# Cable_Tester.net
KiCad netlist of a schematic drawn in EAGLE
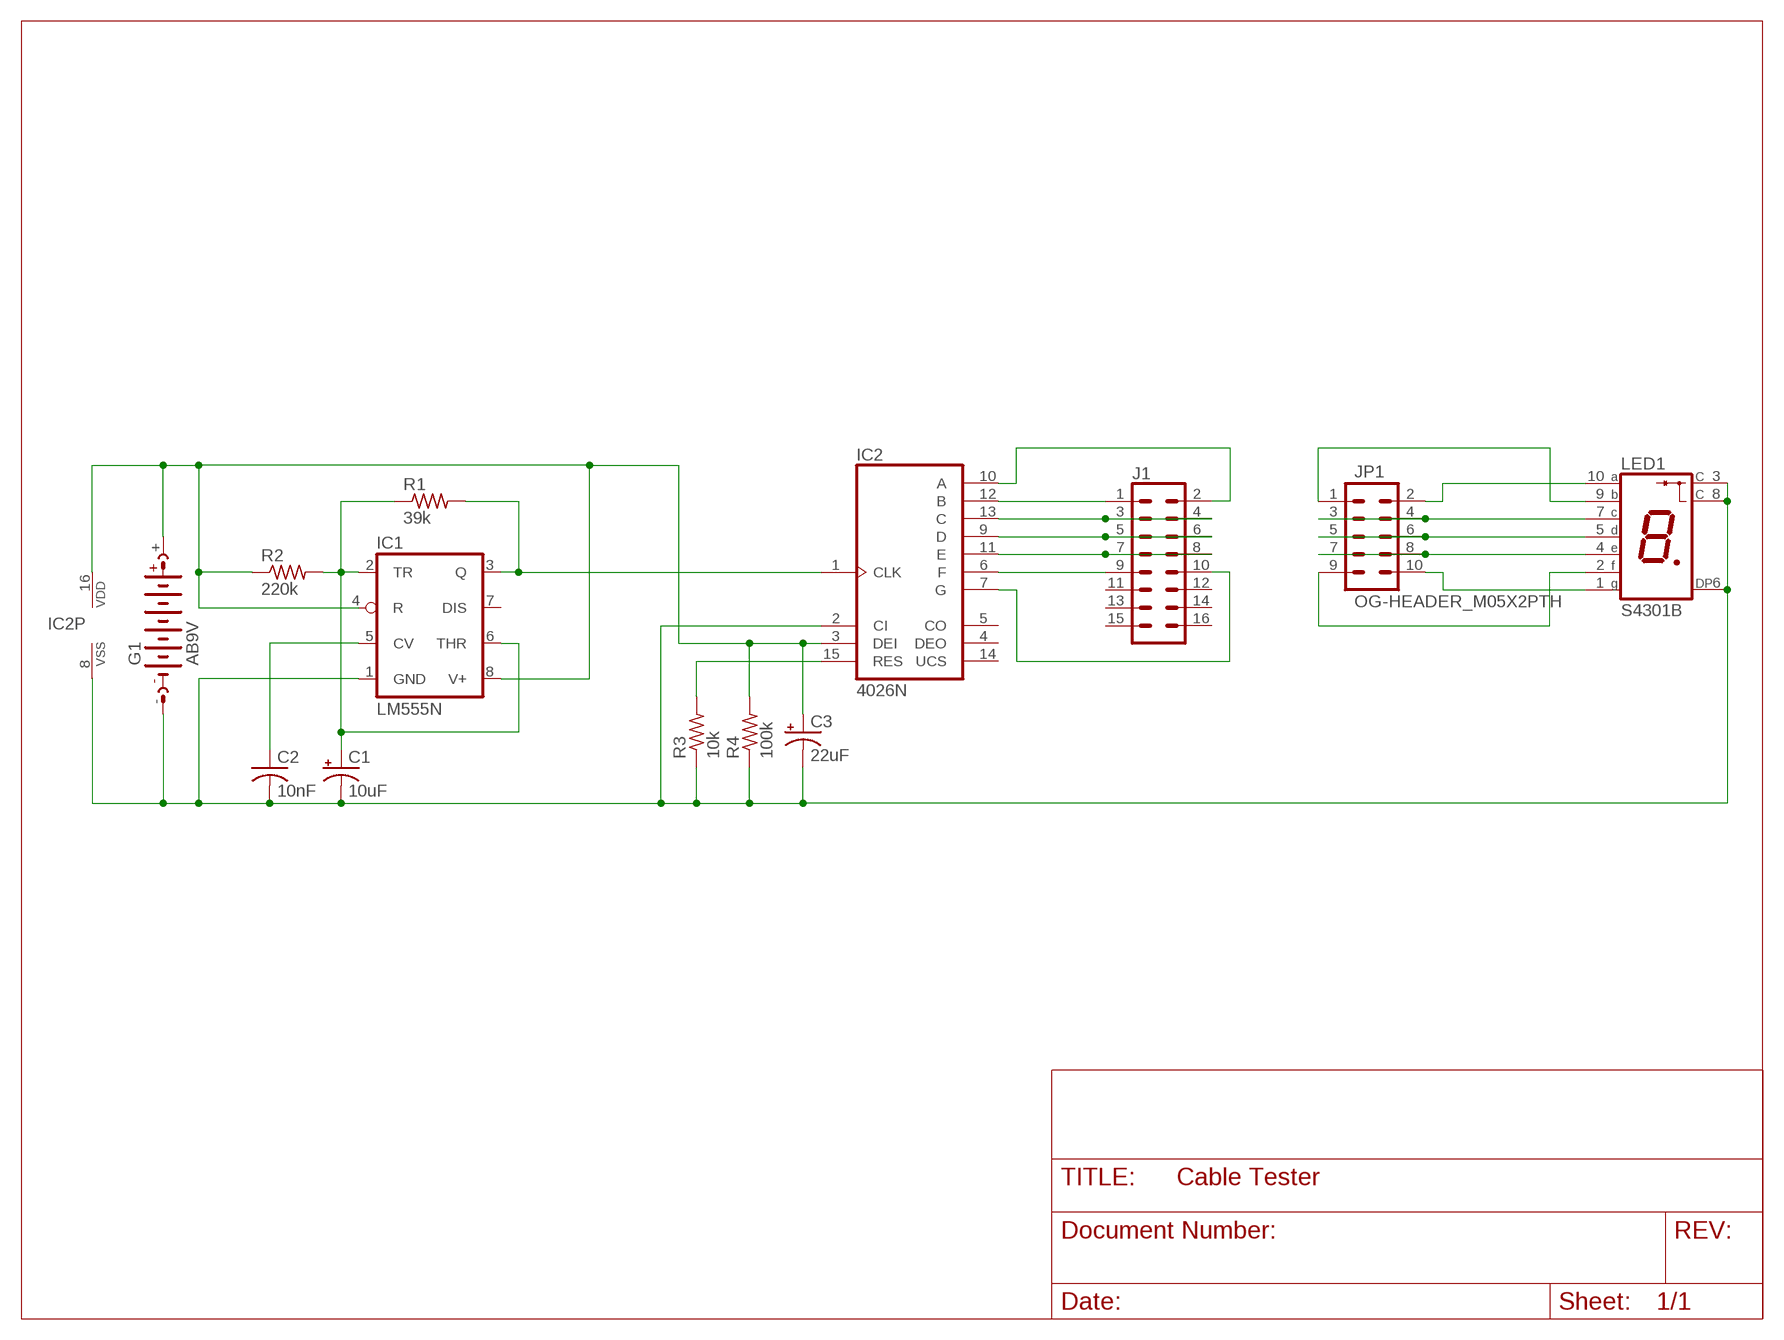
[diagram p0: schematic, sheet 1]

(export (version "E")
  (design (tool "Eeschema 10.0.6"))
  (components
    (comp (ref "C1")
      (value "10uF")
      (footprint "eagle-import:RCL_E5-5")
      (libsource (lib "eagle-import") (part "RCL_CPOL-USE5-5"))
    )
    (comp (ref "C2")
      (value "10nF")
      (footprint "eagle-import:RCL_C050-055X075")
      (libsource (lib "eagle-import") (part "RCL_C-US050-055X075"))
    )
    (comp (ref "C3")
      (value "22uF")
      (footprint "eagle-import:RCL_E5-5")
      (libsource (lib "eagle-import") (part "RCL_CPOL-USE5-5"))
    )
    (comp (ref "G1")
      (value "AB9V")
      (footprint "eagle-import:AB9V")
      (libsource (lib "eagle-import") (part "AB9V"))
    )
    (comp (ref "IC1")
      (value "LM555N")
      (footprint "eagle-import:DIL08")
      (libsource (lib "eagle-import") (part "555NLM"))
    )
    (comp (ref "IC2")
      (value "4026N")
      (footprint "eagle-import:DIL16")
      (libsource (lib "eagle-import") (part "4026N"))
    )
    (comp (ref "J1")
      (value "CONN_08X2_HEADER")
      (footprint "eagle-import:2X8")
      (libsource (lib "eagle-import") (part "CONN_08X2_HEADER"))
    )
    (comp (ref "JP1")
      (value "OG-HEADER_M05X2PTH")
      (footprint "eagle-import:OG-HEADER_AVR_ICSP")
      (libsource (lib "eagle-import") (part "OG-HEADER_M05X2PTH"))
    )
    (comp (ref "LED1")
      (value "S4301B")
      (footprint "eagle-import:S4301B")
      (libsource (lib "eagle-import") (part "S4301B"))
    )
    (comp (ref "R1")
      (value "39k")
      (footprint "eagle-import:RESISTOR_0309_10")
      (libsource (lib "eagle-import") (part "RESISTOR_R-US_0309/10"))
    )
    (comp (ref "R2")
      (value "220k")
      (footprint "eagle-import:RESISTOR_0309_10")
      (libsource (lib "eagle-import") (part "RESISTOR_R-US_0309/10"))
    )
    (comp (ref "R3")
      (value "10k")
      (footprint "eagle-import:RESISTOR_0309_10")
      (libsource (lib "eagle-import") (part "RESISTOR_R-US_0309/10"))
    )
    (comp (ref "R4")
      (value "100k")
      (footprint "eagle-import:RESISTOR_0309_10")
      (libsource (lib "eagle-import") (part "RESISTOR_R-US_0309/10"))
    )
  )
  (nets
    (net (code "1") (name "Net-(IC1-CV)") (class "Default")
      (node (ref "C2") (pin "1") (pinfunction "1_1") (pintype "passive"))
      (node (ref "IC1") (pin "5") (pinfunction "CV_5") (pintype "input"))
    )
    (net (code "2") (name "Net-(IC1-GND)") (class "Default")
      (node (ref "C1") (pin "-") (pinfunction "-_-") (pintype "passive"))
      (node (ref "C2") (pin "2") (pinfunction "2_2") (pintype "passive"))
      (node (ref "C3") (pin "-") (pinfunction "-_-") (pintype "passive"))
      (node (ref "G1") (pin "-") (pinfunction "-_-") (pintype "passive"))
      (node (ref "IC1") (pin "1") (pinfunction "GND_1") (pintype "power_in"))
      (node (ref "IC2") (pin "2") (pinfunction "CI_2") (pintype "input"))
      (node (ref "IC2") (pin "8") (pinfunction "VSS_8") (pintype "power_in"))
      (node (ref "LED1") (pin "3") (pinfunction "C_3") (pintype "passive"))
      (node (ref "LED1") (pin "6") (pinfunction "DP_6") (pintype "passive"))
      (node (ref "LED1") (pin "8") (pinfunction "C_8") (pintype "passive"))
      (node (ref "R3") (pin "1") (pinfunction "1_1") (pintype "passive"))
      (node (ref "R4") (pin "1") (pinfunction "1_1") (pintype "passive"))
    )
    (net (code "3") (name "Net-(IC1-Q)") (class "Default")
      (node (ref "IC1") (pin "3") (pinfunction "Q_3") (pintype "output"))
      (node (ref "IC2") (pin "1") (pinfunction "CLK_1") (pintype "input"))
      (node (ref "R1") (pin "2") (pinfunction "2_2") (pintype "passive"))
    )
    (net (code "4") (name "Net-(IC1-R)") (class "Default")
      (node (ref "C3") (pin "+") (pinfunction "+_+") (pintype "passive"))
      (node (ref "G1") (pin "+") (pinfunction "+_+") (pintype "passive"))
      (node (ref "IC1") (pin "4") (pinfunction "R_4") (pintype "input"))
      (node (ref "IC1") (pin "8") (pinfunction "V+_8") (pintype "power_in"))
      (node (ref "IC2") (pin "16") (pinfunction "VDD_16") (pintype "power_in"))
      (node (ref "IC2") (pin "3") (pinfunction "DEI_3") (pintype "input"))
      (node (ref "R2") (pin "1") (pinfunction "1_1") (pintype "passive"))
      (node (ref "R4") (pin "2") (pinfunction "2_2") (pintype "passive"))
    )
    (net (code "5") (name "Net-(IC1-THR)") (class "Default")
      (node (ref "C1") (pin "+") (pinfunction "+_+") (pintype "passive"))
      (node (ref "IC1") (pin "2") (pinfunction "TR_2") (pintype "input"))
      (node (ref "IC1") (pin "6") (pinfunction "THR_6") (pintype "input"))
      (node (ref "R1") (pin "1") (pinfunction "1_1") (pintype "passive"))
      (node (ref "R2") (pin "2") (pinfunction "2_2") (pintype "passive"))
    )
    (net (code "6") (name "Net-(IC2A-A)") (class "Default")
      (node (ref "IC2") (pin "10") (pinfunction "A_10") (pintype "output"))
      (node (ref "J1") (pin "2") (pinfunction "2_2") (pintype "passive"))
    )
    (net (code "7") (name "Net-(IC2A-B)") (class "Default")
      (node (ref "IC2") (pin "12") (pinfunction "B_12") (pintype "output"))
      (node (ref "J1") (pin "1") (pinfunction "1_1") (pintype "passive"))
    )
    (net (code "8") (name "Net-(IC2A-C)") (class "Default")
      (node (ref "IC2") (pin "13") (pinfunction "C_13") (pintype "output"))
      (node (ref "J1") (pin "3") (pinfunction "3_3") (pintype "passive"))
      (node (ref "J1") (pin "4") (pinfunction "4_4") (pintype "passive"))
    )
    (net (code "9") (name "Net-(IC2A-D)") (class "Default")
      (node (ref "IC2") (pin "9") (pinfunction "D_9") (pintype "output"))
      (node (ref "J1") (pin "5") (pinfunction "5_5") (pintype "passive"))
      (node (ref "J1") (pin "6") (pinfunction "6_6") (pintype "passive"))
    )
    (net (code "10") (name "Net-(IC2A-E)") (class "Default")
      (node (ref "IC2") (pin "11") (pinfunction "E_11") (pintype "output"))
      (node (ref "J1") (pin "7") (pinfunction "7_7") (pintype "passive"))
      (node (ref "J1") (pin "8") (pinfunction "8_8") (pintype "passive"))
    )
    (net (code "11") (name "Net-(IC2A-F)") (class "Default")
      (node (ref "IC2") (pin "6") (pinfunction "F_6") (pintype "output"))
      (node (ref "J1") (pin "9") (pinfunction "9_9") (pintype "passive"))
    )
    (net (code "12") (name "Net-(IC2A-G)") (class "Default")
      (node (ref "IC2") (pin "7") (pinfunction "G_7") (pintype "output"))
      (node (ref "J1") (pin "10") (pinfunction "10_10") (pintype "passive"))
    )
    (net (code "13") (name "Net-(IC2A-RES)") (class "Default")
      (node (ref "IC2") (pin "15") (pinfunction "RES_15") (pintype "input"))
      (node (ref "R3") (pin "2") (pinfunction "2_2") (pintype "passive"))
    )
    (net (code "14") (name "Net-(JP1-Pad3)") (class "Default")
      (node (ref "JP1") (pin "3") (pinfunction "3_3") (pintype "passive"))
      (node (ref "JP1") (pin "4") (pinfunction "4_4") (pintype "passive"))
      (node (ref "LED1") (pin "7") (pinfunction "C_7") (pintype "passive"))
    )
    (net (code "15") (name "Net-(LED1-A)") (class "Default")
      (node (ref "JP1") (pin "2") (pinfunction "2_2") (pintype "passive"))
      (node (ref "LED1") (pin "10") (pinfunction "A_10") (pintype "passive"))
    )
    (net (code "16") (name "Net-(LED1-B)") (class "Default")
      (node (ref "JP1") (pin "1") (pinfunction "1_1") (pintype "passive"))
      (node (ref "LED1") (pin "9") (pinfunction "B_9") (pintype "passive"))
    )
    (net (code "17") (name "Net-(LED1-D)") (class "Default")
      (node (ref "JP1") (pin "5") (pinfunction "5_5") (pintype "passive"))
      (node (ref "JP1") (pin "6") (pinfunction "6_6") (pintype "passive"))
      (node (ref "LED1") (pin "5") (pinfunction "D_5") (pintype "passive"))
    )
    (net (code "18") (name "Net-(LED1-E)") (class "Default")
      (node (ref "JP1") (pin "7") (pinfunction "7_7") (pintype "passive"))
      (node (ref "JP1") (pin "8") (pinfunction "8_8") (pintype "passive"))
      (node (ref "LED1") (pin "4") (pinfunction "E_4") (pintype "passive"))
    )
    (net (code "19") (name "Net-(LED1-F)") (class "Default")
      (node (ref "JP1") (pin "9") (pinfunction "9_9") (pintype "passive"))
      (node (ref "LED1") (pin "2") (pinfunction "F_2") (pintype "passive"))
    )
    (net (code "20") (name "Net-(LED1-G)") (class "Default")
      (node (ref "JP1") (pin "10") (pinfunction "10_10") (pintype "passive"))
      (node (ref "LED1") (pin "1") (pinfunction "G_1") (pintype "passive"))
    )
    (net (code "21") (name "unconnected-(IC1-DIS-Pad7)") (class "Default")
      (node (ref "IC1") (pin "7") (pinfunction "DIS_7") (pintype "input"))
    )
    (net (code "22") (name "unconnected-(IC2A-CO-Pad5)") (class "Default")
      (node (ref "IC2") (pin "5") (pinfunction "CO_5") (pintype "output"))
    )
    (net (code "23") (name "unconnected-(IC2A-DEO-Pad4)") (class "Default")
      (node (ref "IC2") (pin "4") (pinfunction "DEO_4") (pintype "output"))
    )
    (net (code "24") (name "unconnected-(IC2A-UCS-Pad14)") (class "Default")
      (node (ref "IC2") (pin "14") (pinfunction "UCS_14") (pintype "output"))
    )
    (net (code "25") (name "unconnected-(J1-Pad11)") (class "Default")
      (node (ref "J1") (pin "11") (pinfunction "11_11") (pintype "passive"))
    )
    (net (code "26") (name "unconnected-(J1-Pad12)") (class "Default")
      (node (ref "J1") (pin "12") (pinfunction "12_12") (pintype "passive"))
    )
    (net (code "27") (name "unconnected-(J1-Pad13)") (class "Default")
      (node (ref "J1") (pin "13") (pinfunction "13_13") (pintype "passive"))
    )
    (net (code "28") (name "unconnected-(J1-Pad14)") (class "Default")
      (node (ref "J1") (pin "14") (pinfunction "14_14") (pintype "passive"))
    )
    (net (code "29") (name "unconnected-(J1-Pad15)") (class "Default")
      (node (ref "J1") (pin "15") (pinfunction "15_15") (pintype "passive"))
    )
    (net (code "30") (name "unconnected-(J1-Pad16)") (class "Default")
      (node (ref "J1") (pin "16") (pinfunction "16_16") (pintype "passive"))
    )
  )
)
